# Arduino.net
KiCad netlist of a schematic drawn in EAGLE
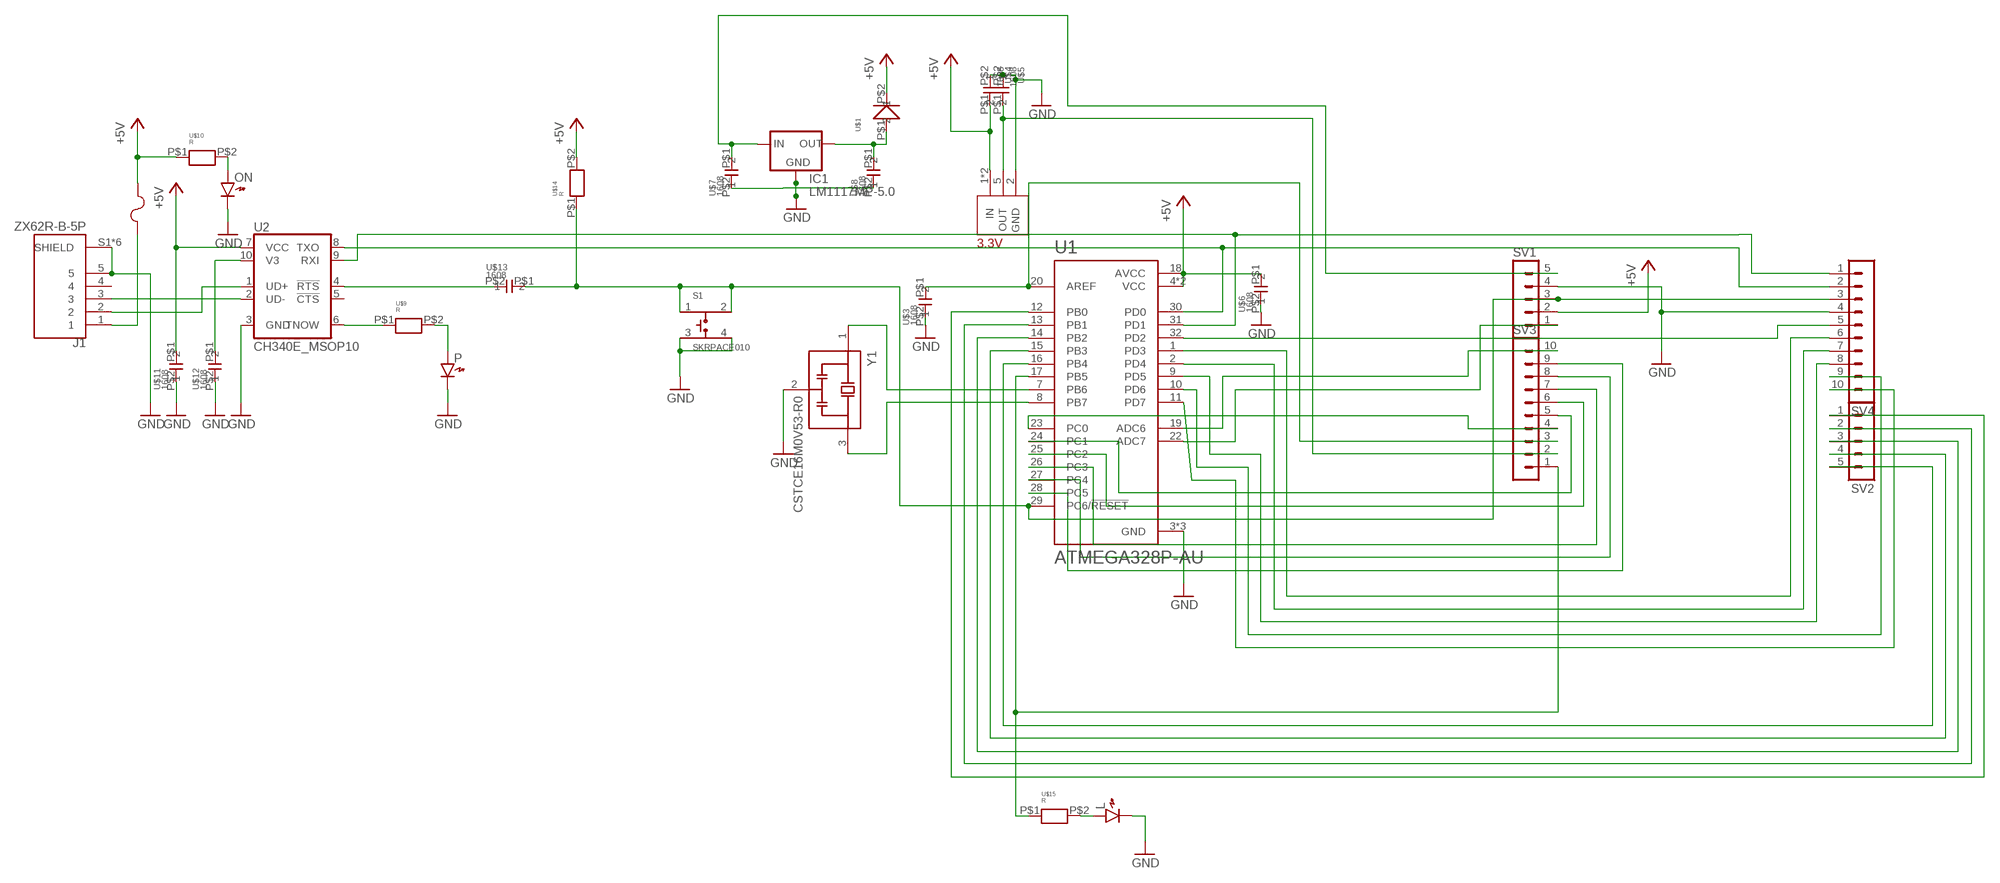
[diagram p0: schematic, sheet 1]

(export (version "E")
  (design (tool "Eeschema 10.0.6"))
  (components
    (comp (ref "IC1")
      (value "LM1117MP-5.0")
      (footprint "eagle-import:SOT223")
      (fields (field (name "MF") "Texas Instruments"))
      (libsource (lib "eagle-import") (part "LM1117?-MP5.0"))
    )
    (comp (ref "J1")
      (value "ZX62R-B-5P")
      (footprint "eagle-import:HRS_ZX62R-B-5P")
      (fields (field (name "MF") "Hirose"))
      (libsource (lib "eagle-import") (part "ZX62R-B-5P"))
    )
    (comp (ref "L")
      (value "LED1608")
      (footprint "eagle-import:LED1608")
      (libsource (lib "eagle-import") (part "LED1608"))
    )
    (comp (ref "ON")
      (value "LED1608")
      (footprint "eagle-import:LED1608")
      (libsource (lib "eagle-import") (part "LED1608"))
    )
    (comp (ref "P")
      (value "LED1608")
      (footprint "eagle-import:LED1608")
      (libsource (lib "eagle-import") (part "LED1608"))
    )
    (comp (ref "S1")
      (value "SKRPACE010")
      (footprint "eagle-import:SW_SKRPACE010")
      (fields (field (name "MF") "ALPS"))
      (libsource (lib "eagle-import") (part "SKRPACE010"))
    )
    (comp (ref "SV1")
      (value "MA05-1")
      (footprint "eagle-import:MA05-1")
      (libsource (lib "eagle-import") (part "MA05-1"))
    )
    (comp (ref "SV2")
      (value "MA05-1")
      (footprint "eagle-import:MA05-1")
      (libsource (lib "eagle-import") (part "MA05-1"))
    )
    (comp (ref "SV3")
      (value "MA10-1")
      (footprint "eagle-import:MA10-1")
      (libsource (lib "eagle-import") (part "MA10-1"))
    )
    (comp (ref "SV4")
      (value "MA10-1")
      (footprint "eagle-import:MA10-1")
      (libsource (lib "eagle-import") (part "MA10-1"))
    )
    (comp (ref "U$1") (value "D") (footprint "eagle-import:D") (libsource (lib "eagle-import") (part "D")))
    (comp (ref "U$2")
      (value "3.3V")
      (footprint "eagle-import:SOT95P285X140-5N")
      (libsource (lib "eagle-import") (part "3.3V"))
    )
    (comp (ref "U$3")
      (value "1608")
      (footprint "eagle-import:CON")
      (libsource (lib "eagle-import") (part "1608"))
    )
    (comp (ref "U$4")
      (value "1608")
      (footprint "eagle-import:CON")
      (libsource (lib "eagle-import") (part "1608"))
    )
    (comp (ref "U$5")
      (value "1608")
      (footprint "eagle-import:CON")
      (libsource (lib "eagle-import") (part "1608"))
    )
    (comp (ref "U$6")
      (value "1608")
      (footprint "eagle-import:CON")
      (libsource (lib "eagle-import") (part "1608"))
    )
    (comp (ref "U$7")
      (value "1608")
      (footprint "eagle-import:CON")
      (libsource (lib "eagle-import") (part "1608"))
    )
    (comp (ref "U$8")
      (value "1608")
      (footprint "eagle-import:CON")
      (libsource (lib "eagle-import") (part "1608"))
    )
    (comp (ref "U$9") (value "R") (footprint "eagle-import:1608") (libsource (lib "eagle-import") (part "R")))
    (comp (ref "U$10")
      (value "R")
      (footprint "eagle-import:1608")
      (libsource (lib "eagle-import") (part "R"))
    )
    (comp (ref "U$11")
      (value "1608")
      (footprint "eagle-import:CON")
      (libsource (lib "eagle-import") (part "1608"))
    )
    (comp (ref "U$12")
      (value "1608")
      (footprint "eagle-import:CON")
      (libsource (lib "eagle-import") (part "1608"))
    )
    (comp (ref "U$13")
      (value "1608")
      (footprint "eagle-import:CON")
      (libsource (lib "eagle-import") (part "1608"))
    )
    (comp (ref "U$14")
      (value "R")
      (footprint "eagle-import:1608")
      (libsource (lib "eagle-import") (part "R"))
    )
    (comp (ref "U$15")
      (value "R")
      (footprint "eagle-import:1608")
      (libsource (lib "eagle-import") (part "R"))
    )
    (comp (ref "U$16") (value "F") (footprint "eagle-import:F") (libsource (lib "eagle-import") (part "F")))
    (comp (ref "U1")
      (value "ATMEGA328P-AU")
      (footprint "eagle-import:QFP80P900X900X120-32N")
      (fields (field (name "MF") "Microchip Technology"))
      (libsource (lib "eagle-import") (part "ATMEGA328P-AU"))
    )
    (comp (ref "U2")
      (value "CH340E_MSOP10")
      (footprint "eagle-import:MSOP10")
      (fields (field (name "MF") "WCH") (field (name "MP") "CH340E"))
      (libsource (lib "eagle-import") (part "CH340E_MSOP10"))
    )
    (comp (ref "Y1")
      (value "CSTCE16M0V53-R0")
      (footprint "eagle-import:OSC_CSTCE16M0V53-R0")
      (fields (field (name "MANUFACTURER") "Murata"))
      (libsource (lib "eagle-import") (part "CSTCE16M0V53-R0"))
    )
  )
  (nets
    (net (code "1") (name "+5V") (class "Default")
      (node (ref "SV1") (pin "2") (pinfunction "2_2") (pintype "passive"))
      (node (ref "U$1") (pin "P$2") (pinfunction "2_P$2") (pintype "bidirectional"))
      (node (ref "U$10") (pin "P$1") (pinfunction "P$1_P$1") (pintype "bidirectional"))
      (node (ref "U$11") (pin "P$1") (pinfunction "1_P$1") (pintype "bidirectional"))
      (node (ref "U$14") (pin "P$2") (pinfunction "P$2_P$2") (pintype "bidirectional"))
      (node (ref "U$16") (pin "P$2") (pinfunction "P$2_P$2") (pintype "bidirectional"))
      (node (ref "U$2") (pin "1") (pinfunction "IN_1") (pintype "bidirectional"))
      (node (ref "U$2") (pin "3") (pinfunction "IN_3") (pintype "bidirectional"))
      (node (ref "U$4") (pin "P$1") (pinfunction "1_P$1") (pintype "bidirectional"))
      (node (ref "U$6") (pin "P$1") (pinfunction "1_P$1") (pintype "bidirectional"))
      (node (ref "U1") (pin "18") (pinfunction "AVCC_18") (pintype "power_in"))
      (node (ref "U1") (pin "4") (pinfunction "VCC_4") (pintype "power_in"))
      (node (ref "U1") (pin "6") (pinfunction "VCC_6") (pintype "power_in"))
      (node (ref "U2") (pin "7") (pinfunction "VCC_7") (pintype "bidirectional"))
    )
    (net (code "2") (name "GND") (class "Default")
      (node (ref "IC1") (pin "1") (pinfunction "GND_1") (pintype "input"))
      (node (ref "J1") (pin "5") (pinfunction "5_5") (pintype "passive"))
      (node (ref "J1") (pin "S1") (pinfunction "SHIELD_S1") (pintype "passive"))
      (node (ref "J1") (pin "S2") (pinfunction "SHIELD_S2") (pintype "passive"))
      (node (ref "J1") (pin "S3") (pinfunction "SHIELD_S3") (pintype "passive"))
      (node (ref "J1") (pin "S4") (pinfunction "SHIELD_S4") (pintype "passive"))
      (node (ref "J1") (pin "S5") (pinfunction "SHIELD_S5") (pintype "passive"))
      (node (ref "J1") (pin "S6") (pinfunction "SHIELD_S6") (pintype "passive"))
      (node (ref "L") (pin "K") (pinfunction "K_K") (pintype "passive"))
      (node (ref "ON") (pin "K") (pinfunction "K_K") (pintype "passive"))
      (node (ref "P") (pin "K") (pinfunction "K_K") (pintype "passive"))
      (node (ref "S1") (pin "3") (pinfunction "3_3") (pintype "bidirectional"))
      (node (ref "S1") (pin "4") (pinfunction "4_4") (pintype "bidirectional"))
      (node (ref "SV1") (pin "4") (pinfunction "4_4") (pintype "passive"))
      (node (ref "SV4") (pin "4") (pinfunction "4_4") (pintype "passive"))
      (node (ref "U$11") (pin "P$2") (pinfunction "2_P$2") (pintype "bidirectional"))
      (node (ref "U$12") (pin "P$2") (pinfunction "2_P$2") (pintype "bidirectional"))
      (node (ref "U$2") (pin "2") (pinfunction "GND_2") (pintype "bidirectional"))
      (node (ref "U$3") (pin "P$2") (pinfunction "2_P$2") (pintype "bidirectional"))
      (node (ref "U$4") (pin "P$2") (pinfunction "2_P$2") (pintype "bidirectional"))
      (node (ref "U$5") (pin "P$2") (pinfunction "2_P$2") (pintype "bidirectional"))
      (node (ref "U$6") (pin "P$2") (pinfunction "2_P$2") (pintype "bidirectional"))
      (node (ref "U$7") (pin "P$2") (pinfunction "2_P$2") (pintype "bidirectional"))
      (node (ref "U$8") (pin "P$2") (pinfunction "2_P$2") (pintype "bidirectional"))
      (node (ref "U1") (pin "21") (pinfunction "GND_21") (pintype "power_in"))
      (node (ref "U1") (pin "3") (pinfunction "GND_3") (pintype "power_in"))
      (node (ref "U1") (pin "5") (pinfunction "GND_5") (pintype "power_in"))
      (node (ref "U2") (pin "3") (pinfunction "GND_3") (pintype "bidirectional"))
      (node (ref "Y1") (pin "2") (pinfunction "GND_2") (pintype "power_in"))
    )
    (net (code "3") (name "Net-(IC1-IN)") (class "Default")
      (node (ref "IC1") (pin "3") (pinfunction "IN_3") (pintype "input"))
      (node (ref "SV1") (pin "5") (pinfunction "5_5") (pintype "passive"))
      (node (ref "U$7") (pin "P$1") (pinfunction "1_P$1") (pintype "bidirectional"))
    )
    (net (code "4") (name "Net-(J1-Pad1)") (class "Default")
      (node (ref "J1") (pin "1") (pinfunction "1_1") (pintype "passive"))
      (node (ref "U$16") (pin "P$1") (pinfunction "P$1_P$1") (pintype "bidirectional"))
    )
    (net (code "5") (name "Net-(L-PadA)") (class "Default")
      (node (ref "L") (pin "A") (pinfunction "A_A") (pintype "passive"))
      (node (ref "U$15") (pin "P$2") (pinfunction "P$2_P$2") (pintype "bidirectional"))
    )
    (net (code "6") (name "Net-(ON-PadA)") (class "Default")
      (node (ref "ON") (pin "A") (pinfunction "A_A") (pintype "passive"))
      (node (ref "U$10") (pin "P$2") (pinfunction "P$2_P$2") (pintype "bidirectional"))
    )
    (net (code "7") (name "Net-(P-PadA)") (class "Default")
      (node (ref "P") (pin "A") (pinfunction "A_A") (pintype "passive"))
      (node (ref "U$9") (pin "P$2") (pinfunction "P$2_P$2") (pintype "bidirectional"))
    )
    (net (code "8") (name "Net-(U$1-1)") (class "Default")
      (node (ref "IC1") (pin "2") (pinfunction "OUT_2") (pintype "passive"))
      (node (ref "IC1") (pin "4") (pinfunction "OUT_4") (pintype "passive"))
      (node (ref "U$1") (pin "P$1") (pinfunction "1_P$1") (pintype "bidirectional"))
      (node (ref "U$8") (pin "P$1") (pinfunction "1_P$1") (pintype "bidirectional"))
    )
    (net (code "9") (name "Net-(U$2-OUT)") (class "Default")
      (node (ref "SV3") (pin "2") (pinfunction "2_2") (pintype "passive"))
      (node (ref "U$2") (pin "5") (pinfunction "OUT_5") (pintype "bidirectional"))
      (node (ref "U$5") (pin "P$1") (pinfunction "1_P$1") (pintype "bidirectional"))
    )
    (net (code "10") (name "Net-(U$3-1)") (class "Default")
      (node (ref "SV3") (pin "3") (pinfunction "3_3") (pintype "passive"))
      (node (ref "U$3") (pin "P$1") (pinfunction "1_P$1") (pintype "bidirectional"))
      (node (ref "U1") (pin "20") (pinfunction "AREF_20") (pintype "input"))
    )
    (net (code "11") (name "Net-(U$12-1)") (class "Default")
      (node (ref "U$12") (pin "P$1") (pinfunction "1_P$1") (pintype "bidirectional"))
      (node (ref "U2") (pin "10") (pinfunction "V3_10") (pintype "bidirectional"))
    )
    (net (code "12") (name "Net-(U$13-1)") (class "Default")
      (node (ref "S1") (pin "1") (pinfunction "1_1") (pintype "bidirectional"))
      (node (ref "S1") (pin "2") (pinfunction "2_2") (pintype "bidirectional"))
      (node (ref "SV1") (pin "3") (pinfunction "3_3") (pintype "passive"))
      (node (ref "SV4") (pin "3") (pinfunction "3_3") (pintype "passive"))
      (node (ref "U$13") (pin "P$1") (pinfunction "1_P$1") (pintype "bidirectional"))
      (node (ref "U$14") (pin "P$1") (pinfunction "P$1_P$1") (pintype "bidirectional"))
      (node (ref "U1") (pin "29") (pinfunction "PC6/~{RESET}_29") (pintype "bidirectional"))
    )
    (net (code "13") (name "Net-(U$13-2)") (class "Default")
      (node (ref "U$13") (pin "P$2") (pinfunction "2_P$2") (pintype "bidirectional"))
      (node (ref "U2") (pin "4") (pinfunction "~{RTS}_4") (pintype "bidirectional"))
    )
    (net (code "14") (name "Net-(U1-ADC6)") (class "Default")
      (node (ref "SV3") (pin "10") (pinfunction "10_10") (pintype "passive"))
      (node (ref "U1") (pin "19") (pinfunction "ADC6_19") (pintype "bidirectional"))
    )
    (net (code "15") (name "Net-(U1-ADC7)") (class "Default")
      (node (ref "SV1") (pin "1") (pinfunction "1_1") (pintype "passive"))
      (node (ref "U1") (pin "22") (pinfunction "ADC7_22") (pintype "bidirectional"))
    )
    (net (code "16") (name "Net-(U1-PB0)") (class "Default")
      (node (ref "SV2") (pin "1") (pinfunction "1_1") (pintype "passive"))
      (node (ref "U1") (pin "12") (pinfunction "PB0_12") (pintype "bidirectional"))
    )
    (net (code "17") (name "Net-(U1-PB1)") (class "Default")
      (node (ref "SV2") (pin "2") (pinfunction "2_2") (pintype "passive"))
      (node (ref "U1") (pin "13") (pinfunction "PB1_13") (pintype "bidirectional"))
    )
    (net (code "18") (name "Net-(U1-PB2)") (class "Default")
      (node (ref "SV2") (pin "3") (pinfunction "3_3") (pintype "passive"))
      (node (ref "U1") (pin "14") (pinfunction "PB2_14") (pintype "bidirectional"))
    )
    (net (code "19") (name "Net-(U1-PB3)") (class "Default")
      (node (ref "SV2") (pin "4") (pinfunction "4_4") (pintype "passive"))
      (node (ref "U1") (pin "15") (pinfunction "PB3_15") (pintype "bidirectional"))
    )
    (net (code "20") (name "Net-(U1-PB4)") (class "Default")
      (node (ref "SV2") (pin "5") (pinfunction "5_5") (pintype "passive"))
      (node (ref "U1") (pin "16") (pinfunction "PB4_16") (pintype "bidirectional"))
    )
    (net (code "21") (name "Net-(U1-PB5)") (class "Default")
      (node (ref "SV3") (pin "1") (pinfunction "1_1") (pintype "passive"))
      (node (ref "U$15") (pin "P$1") (pinfunction "P$1_P$1") (pintype "bidirectional"))
      (node (ref "U1") (pin "17") (pinfunction "PB5_17") (pintype "bidirectional"))
    )
    (net (code "22") (name "Net-(U1-PB6)") (class "Default")
      (node (ref "U1") (pin "7") (pinfunction "PB6_7") (pintype "bidirectional"))
      (node (ref "Y1") (pin "1") (pinfunction "IN_1") (pintype "input"))
    )
    (net (code "23") (name "Net-(U1-PB7)") (class "Default")
      (node (ref "U1") (pin "8") (pinfunction "PB7_8") (pintype "bidirectional"))
      (node (ref "Y1") (pin "3") (pinfunction "OUT_3") (pintype "output"))
    )
    (net (code "24") (name "Net-(U1-PC0)") (class "Default")
      (node (ref "SV3") (pin "4") (pinfunction "4_4") (pintype "passive"))
      (node (ref "U1") (pin "23") (pinfunction "PC0_23") (pintype "bidirectional"))
    )
    (net (code "25") (name "Net-(U1-PC1)") (class "Default")
      (node (ref "SV3") (pin "5") (pinfunction "5_5") (pintype "passive"))
      (node (ref "U1") (pin "24") (pinfunction "PC1_24") (pintype "bidirectional"))
    )
    (net (code "26") (name "Net-(U1-PC2)") (class "Default")
      (node (ref "SV3") (pin "6") (pinfunction "6_6") (pintype "passive"))
      (node (ref "U1") (pin "25") (pinfunction "PC2_25") (pintype "bidirectional"))
    )
    (net (code "27") (name "Net-(U1-PC3)") (class "Default")
      (node (ref "SV3") (pin "7") (pinfunction "7_7") (pintype "passive"))
      (node (ref "U1") (pin "26") (pinfunction "PC3_26") (pintype "bidirectional"))
    )
    (net (code "28") (name "Net-(U1-PC4)") (class "Default")
      (node (ref "SV3") (pin "8") (pinfunction "8_8") (pintype "passive"))
      (node (ref "U1") (pin "27") (pinfunction "PC4_27") (pintype "bidirectional"))
    )
    (net (code "29") (name "Net-(U1-PC5)") (class "Default")
      (node (ref "SV3") (pin "9") (pinfunction "9_9") (pintype "passive"))
      (node (ref "U1") (pin "28") (pinfunction "PC5_28") (pintype "bidirectional"))
    )
    (net (code "30") (name "Net-(U1-PD0)") (class "Default")
      (node (ref "SV4") (pin "2") (pinfunction "2_2") (pintype "passive"))
      (node (ref "U1") (pin "30") (pinfunction "PD0_30") (pintype "bidirectional"))
      (node (ref "U2") (pin "8") (pinfunction "TXO_8") (pintype "bidirectional"))
    )
    (net (code "31") (name "Net-(U1-PD1)") (class "Default")
      (node (ref "SV4") (pin "1") (pinfunction "1_1") (pintype "passive"))
      (node (ref "U1") (pin "31") (pinfunction "PD1_31") (pintype "bidirectional"))
      (node (ref "U2") (pin "9") (pinfunction "RXI_9") (pintype "bidirectional"))
    )
    (net (code "32") (name "Net-(U1-PD2)") (class "Default")
      (node (ref "SV4") (pin "5") (pinfunction "5_5") (pintype "passive"))
      (node (ref "U1") (pin "32") (pinfunction "PD2_32") (pintype "bidirectional"))
    )
    (net (code "33") (name "Net-(U1-PD3)") (class "Default")
      (node (ref "SV4") (pin "6") (pinfunction "6_6") (pintype "passive"))
      (node (ref "U1") (pin "1") (pinfunction "PD3_1") (pintype "bidirectional"))
    )
    (net (code "34") (name "Net-(U1-PD4)") (class "Default")
      (node (ref "SV4") (pin "7") (pinfunction "7_7") (pintype "passive"))
      (node (ref "U1") (pin "2") (pinfunction "PD4_2") (pintype "bidirectional"))
    )
    (net (code "35") (name "Net-(U1-PD5)") (class "Default")
      (node (ref "SV4") (pin "8") (pinfunction "8_8") (pintype "passive"))
      (node (ref "U1") (pin "9") (pinfunction "PD5_9") (pintype "bidirectional"))
    )
    (net (code "36") (name "Net-(U1-PD6)") (class "Default")
      (node (ref "SV4") (pin "9") (pinfunction "9_9") (pintype "passive"))
      (node (ref "U1") (pin "10") (pinfunction "PD6_10") (pintype "bidirectional"))
    )
    (net (code "37") (name "Net-(U1-PD7)") (class "Default")
      (node (ref "SV4") (pin "10") (pinfunction "10_10") (pintype "passive"))
      (node (ref "U1") (pin "11") (pinfunction "PD7_11") (pintype "bidirectional"))
    )
    (net (code "38") (name "Net-(U2-TNOW)") (class "Default")
      (node (ref "U$9") (pin "P$1") (pinfunction "P$1_P$1") (pintype "bidirectional"))
      (node (ref "U2") (pin "6") (pinfunction "TNOW_6") (pintype "bidirectional"))
    )
    (net (code "39") (name "Net-(U2-UD+)") (class "Default")
      (node (ref "J1") (pin "2") (pinfunction "2_2") (pintype "passive"))
      (node (ref "U2") (pin "1") (pinfunction "UD+_1") (pintype "bidirectional"))
    )
    (net (code "40") (name "Net-(U2-UD-)") (class "Default")
      (node (ref "J1") (pin "3") (pinfunction "3_3") (pintype "passive"))
      (node (ref "U2") (pin "2") (pinfunction "UD-_2") (pintype "bidirectional"))
    )
    (net (code "41") (name "unconnected-(J1-Pad4)") (class "Default")
      (node (ref "J1") (pin "4") (pinfunction "4_4") (pintype "passive"))
    )
    (net (code "42") (name "unconnected-(U2-~{CTS}-Pad5)") (class "Default")
      (node (ref "U2") (pin "5") (pinfunction "~{CTS}_5") (pintype "bidirectional"))
    )
  )
)
